# EC544.net
KiCad netlist of a schematic drawn in EAGLE
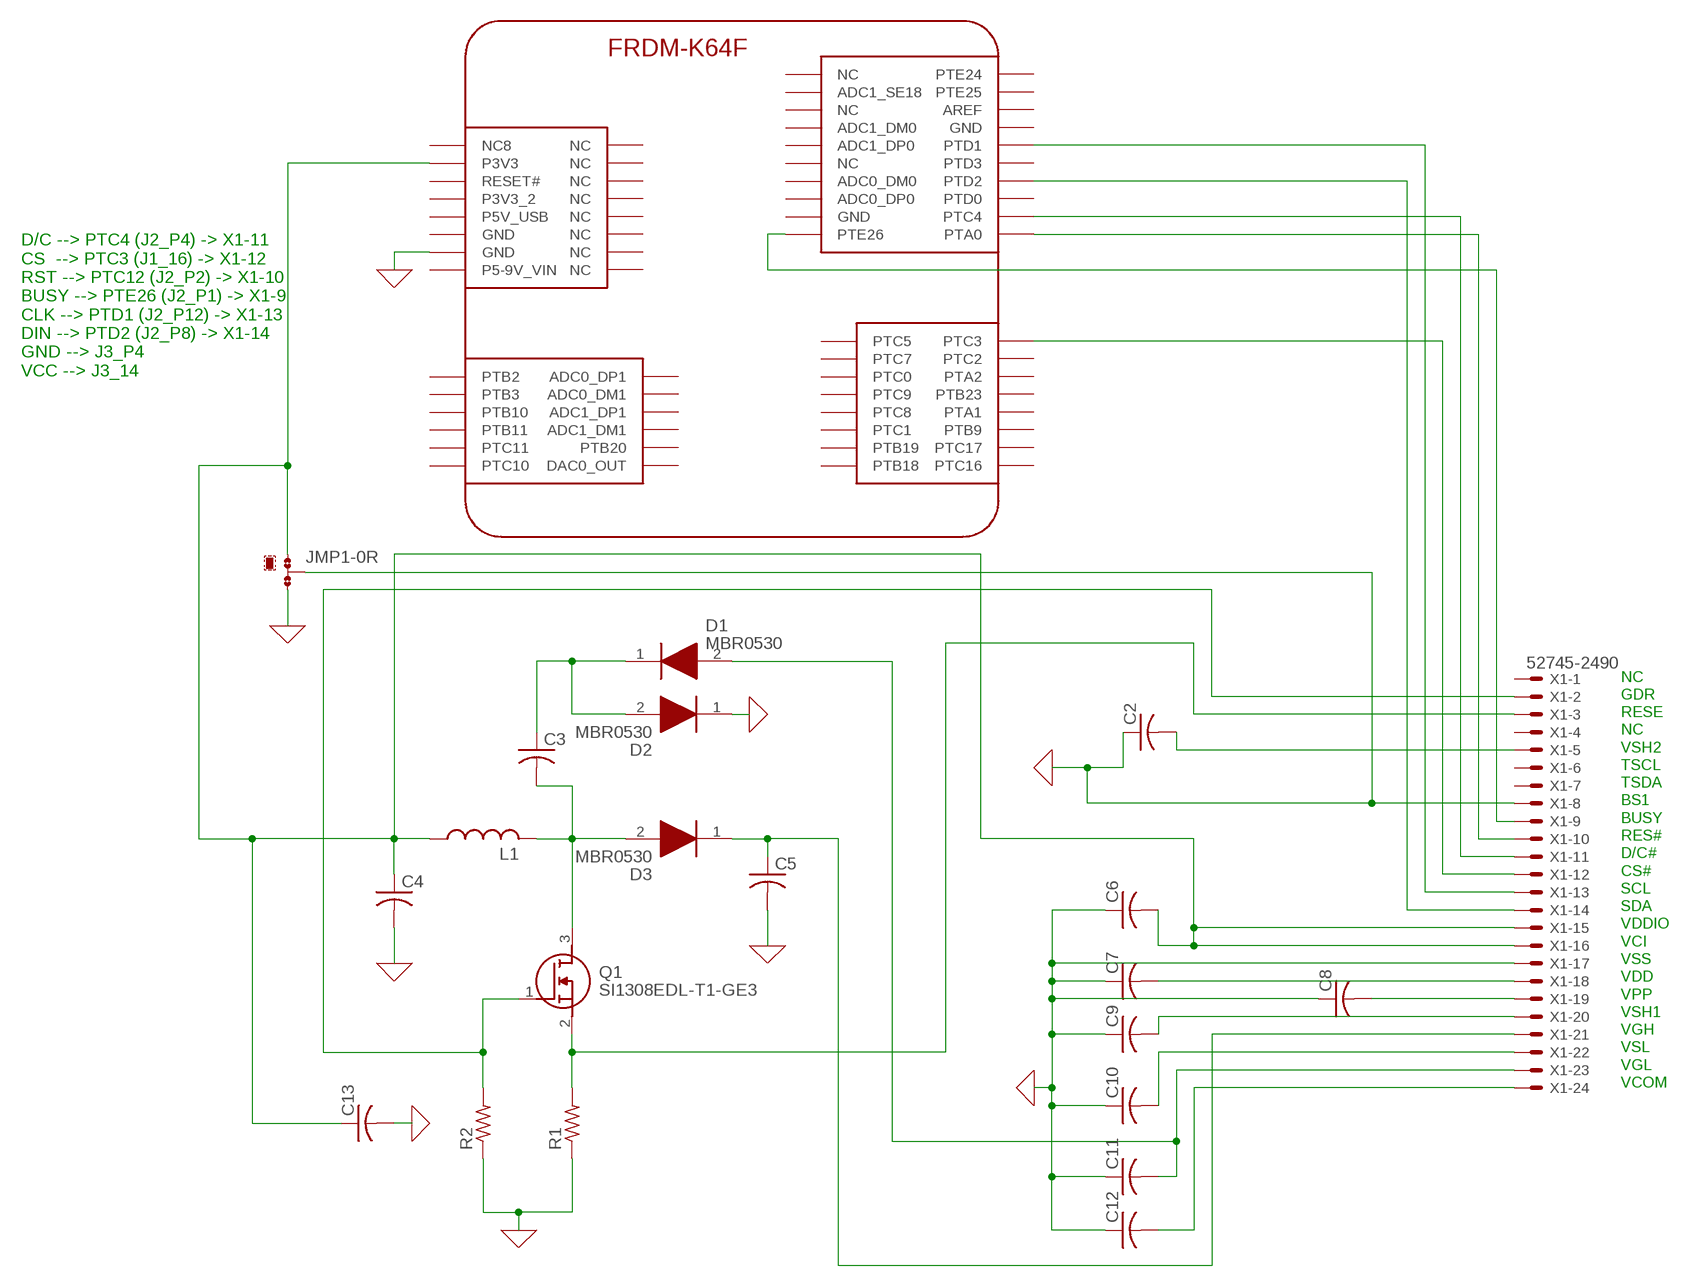
[diagram p0: schematic, sheet 1]

(export (version "E")
  (design (tool "Eeschema 10.0.6"))
  (components
    (comp (ref "C2")
      (value "C-US025-024X044")
      (footprint "eagle-import:C025-024X044")
      (libsource (lib "eagle-import") (part "C-US025-024X044"))
    )
    (comp (ref "C3")
      (value "C-US025-024X044")
      (footprint "eagle-import:C025-024X044")
      (libsource (lib "eagle-import") (part "C-US025-024X044"))
    )
    (comp (ref "C4")
      (value "C-US025-024X044")
      (footprint "eagle-import:C025-024X044")
      (libsource (lib "eagle-import") (part "C-US025-024X044"))
    )
    (comp (ref "C5")
      (value "C-US025-024X044")
      (footprint "eagle-import:C025-024X044")
      (libsource (lib "eagle-import") (part "C-US025-024X044"))
    )
    (comp (ref "C6")
      (value "C-US025-024X044")
      (footprint "eagle-import:C025-024X044")
      (libsource (lib "eagle-import") (part "C-US025-024X044"))
    )
    (comp (ref "C7")
      (value "C-US025-024X044")
      (footprint "eagle-import:C025-024X044")
      (libsource (lib "eagle-import") (part "C-US025-024X044"))
    )
    (comp (ref "C8")
      (value "C-US025-024X044")
      (footprint "eagle-import:C025-024X044")
      (libsource (lib "eagle-import") (part "C-US025-024X044"))
    )
    (comp (ref "C9")
      (value "C-US025-024X044")
      (footprint "eagle-import:C025-024X044")
      (libsource (lib "eagle-import") (part "C-US025-024X044"))
    )
    (comp (ref "C10")
      (value "C-US025-024X044")
      (footprint "eagle-import:C025-024X044")
      (libsource (lib "eagle-import") (part "C-US025-024X044"))
    )
    (comp (ref "C11")
      (value "C-US025-024X044")
      (footprint "eagle-import:C025-024X044")
      (libsource (lib "eagle-import") (part "C-US025-024X044"))
    )
    (comp (ref "C12")
      (value "C-US025-024X044")
      (footprint "eagle-import:C025-024X044")
      (libsource (lib "eagle-import") (part "C-US025-024X044"))
    )
    (comp (ref "C13")
      (value "C-US025-024X044")
      (footprint "eagle-import:C025-024X044")
      (libsource (lib "eagle-import") (part "C-US025-024X044"))
    )
    (comp (ref "D1")
      (value "MBR0530")
      (footprint "eagle-import:SOD3716X135N")
      (fields (field (name "MOUSER_PART_NUMBER") "512-MBR0530"))
      (libsource (lib "eagle-import") (part "MBR0530"))
    )
    (comp (ref "D2")
      (value "MBR0530")
      (footprint "eagle-import:SOD3716X135N")
      (fields (field (name "MOUSER_PART_NUMBER") "512-MBR0530"))
      (libsource (lib "eagle-import") (part "MBR0530"))
    )
    (comp (ref "D3")
      (value "MBR0530")
      (footprint "eagle-import:SOD3716X135N")
      (fields (field (name "MOUSER_PART_NUMBER") "512-MBR0530"))
      (libsource (lib "eagle-import") (part "MBR0530"))
    )
    (comp (ref "FRDM1")
      (value "FRDM-K64FNORMAL")
      (footprint "eagle-import:FRDM_K64F")
      (libsource (lib "eagle-import") (part "FRDM-K64FNORMAL"))
    )
    (comp (ref "JMP1")
      (value "0R-JUMPA")
      (footprint "eagle-import:A0R-JMP")
      (libsource (lib "eagle-import") (part "0R-JUMPA"))
    )
    (comp (ref "L1")
      (value "L-USPIS2816")
      (footprint "eagle-import:PIS2816")
      (libsource (lib "eagle-import") (part "L-USPIS2816"))
    )
    (comp (ref "Q1")
      (value "SI1308EDL-T1-GE3")
      (footprint "eagle-import:SOT65P210X110-3N")
      (fields
        (field (name "MANUFACTURER_PART_NUMBER") "Si1308EDL-T1-GE3")
        (field (name "MOUSER_PART_NUMBER") "78-SI1308EDL-T1-GE3")
      )
      (libsource (lib "eagle-import") (part "SI1308EDL-T1-GE3"))
    )
    (comp (ref "R1")
      (value "R-US_0204/5")
      (footprint "eagle-import:0204_5")
      (libsource (lib "eagle-import") (part "R-US_0204/5"))
    )
    (comp (ref "R2")
      (value "R-US_0204/5")
      (footprint "eagle-import:0204_5")
      (libsource (lib "eagle-import") (part "R-US_0204/5"))
    )
    (comp (ref "X1")
      (value "52745-2490")
      (footprint "eagle-import:52745-2490")
      (fields (field (name "MF") "MOLEX"))
      (libsource (lib "eagle-import") (part "52745-2490"))
    )
  )
  (nets
    (net (code "1") (name "GND") (class "Default")
      (node (ref "C10") (pin "1") (pinfunction "1_1") (pintype "passive"))
      (node (ref "C11") (pin "1") (pinfunction "1_1") (pintype "passive"))
      (node (ref "C12") (pin "1") (pinfunction "1_1") (pintype "passive"))
      (node (ref "C13") (pin "2") (pinfunction "2_2") (pintype "passive"))
      (node (ref "C2") (pin "1") (pinfunction "1_1") (pintype "passive"))
      (node (ref "C4") (pin "2") (pinfunction "2_2") (pintype "passive"))
      (node (ref "C5") (pin "2") (pinfunction "2_2") (pintype "passive"))
      (node (ref "C6") (pin "1") (pinfunction "1_1") (pintype "passive"))
      (node (ref "C7") (pin "1") (pinfunction "1_1") (pintype "passive"))
      (node (ref "C8") (pin "1") (pinfunction "1_1") (pintype "passive"))
      (node (ref "C9") (pin "1") (pinfunction "1_1") (pintype "passive"))
      (node (ref "D2") (pin "1") (pinfunction "K_1") (pintype "bidirectional"))
      (node (ref "FRDM1") (pin "J3.14") (pinfunction "GND_J3.14") (pintype "bidirectional"))
      (node (ref "JMP1") (pin "2") (pinfunction "2_2") (pintype "passive"))
      (node (ref "JMP1") (pin "3") (pinfunction "3_3") (pintype "passive"))
      (node (ref "R1") (pin "1") (pinfunction "1_1") (pintype "passive"))
      (node (ref "R2") (pin "1") (pinfunction "1_1") (pintype "passive"))
      (node (ref "X1") (pin "17") (pinfunction "S_17") (pintype "passive"))
      (node (ref "X1") (pin "8") (pinfunction "S_8") (pintype "passive"))
    )
    (net (code "2") (name "Net-(D1-A)") (class "Default")
      (node (ref "C11") (pin "2") (pinfunction "2_2") (pintype "passive"))
      (node (ref "D1") (pin "2") (pinfunction "A_2") (pintype "bidirectional"))
      (node (ref "X1") (pin "23") (pinfunction "S_23") (pintype "passive"))
    )
    (net (code "3") (name "Net-(D1-K)") (class "Default")
      (node (ref "C3") (pin "1") (pinfunction "1_1") (pintype "passive"))
      (node (ref "D1") (pin "1") (pinfunction "K_1") (pintype "bidirectional"))
      (node (ref "D2") (pin "2") (pinfunction "A_2") (pintype "bidirectional"))
    )
    (net (code "4") (name "Net-(D3-A)") (class "Default")
      (node (ref "C3") (pin "2") (pinfunction "2_2") (pintype "passive"))
      (node (ref "D3") (pin "2") (pinfunction "A_2") (pintype "bidirectional"))
      (node (ref "L1") (pin "2") (pinfunction "2_2") (pintype "passive"))
      (node (ref "Q1") (pin "3") (pinfunction "D_3") (pintype "bidirectional"))
    )
    (net (code "5") (name "Net-(D3-K)") (class "Default")
      (node (ref "C5") (pin "1") (pinfunction "1_1") (pintype "passive"))
      (node (ref "D3") (pin "1") (pinfunction "K_1") (pintype "bidirectional"))
      (node (ref "X1") (pin "21") (pinfunction "S_21") (pintype "passive"))
    )
    (net (code "6") (name "Net-(FRDM1-P3V3)") (class "Default")
      (node (ref "C13") (pin "1") (pinfunction "1_1") (pintype "passive"))
      (node (ref "C4") (pin "1") (pinfunction "1_1") (pintype "passive"))
      (node (ref "C6") (pin "2") (pinfunction "2_2") (pintype "passive"))
      (node (ref "FRDM1") (pin "J3.4") (pinfunction "P3V3_J3.4") (pintype "bidirectional"))
      (node (ref "JMP1") (pin "1") (pinfunction "1_1") (pintype "passive"))
      (node (ref "L1") (pin "1") (pinfunction "1_1") (pintype "passive"))
      (node (ref "X1") (pin "15") (pinfunction "S_15") (pintype "passive"))
      (node (ref "X1") (pin "16") (pinfunction "S_16") (pintype "passive"))
    )
    (net (code "7") (name "Net-(FRDM1-PTA0)") (class "Default")
      (node (ref "FRDM1") (pin "J2.2") (pinfunction "PTA0_J2.2") (pintype "bidirectional"))
      (node (ref "X1") (pin "10") (pinfunction "S_10") (pintype "passive"))
    )
    (net (code "8") (name "Net-(FRDM1-PTC3)") (class "Default")
      (node (ref "FRDM1") (pin "J1.16") (pinfunction "PTC3_J1.16") (pintype "bidirectional"))
      (node (ref "X1") (pin "12") (pinfunction "S_12") (pintype "passive"))
    )
    (net (code "9") (name "Net-(FRDM1-PTC4)") (class "Default")
      (node (ref "FRDM1") (pin "J2.4") (pinfunction "PTC4_J2.4") (pintype "bidirectional"))
      (node (ref "X1") (pin "11") (pinfunction "S_11") (pintype "passive"))
    )
    (net (code "10") (name "Net-(FRDM1-PTD1)") (class "Default")
      (node (ref "FRDM1") (pin "J2.12") (pinfunction "PTD1_J2.12") (pintype "bidirectional"))
      (node (ref "X1") (pin "13") (pinfunction "S_13") (pintype "passive"))
    )
    (net (code "11") (name "Net-(FRDM1-PTD2)") (class "Default")
      (node (ref "FRDM1") (pin "J2.8") (pinfunction "PTD2_J2.8") (pintype "bidirectional"))
      (node (ref "X1") (pin "14") (pinfunction "S_14") (pintype "passive"))
    )
    (net (code "12") (name "Net-(FRDM1-PTE26)") (class "Default")
      (node (ref "FRDM1") (pin "J2.1") (pinfunction "PTE26_J2.1") (pintype "bidirectional"))
      (node (ref "X1") (pin "9") (pinfunction "S_9") (pintype "passive"))
    )
    (net (code "13") (name "Net-(Q1-G)") (class "Default")
      (node (ref "Q1") (pin "1") (pinfunction "G_1") (pintype "bidirectional"))
      (node (ref "R2") (pin "2") (pinfunction "2_2") (pintype "passive"))
      (node (ref "X1") (pin "2") (pinfunction "S_2") (pintype "passive"))
    )
    (net (code "14") (name "Net-(Q1-S)") (class "Default")
      (node (ref "Q1") (pin "2") (pinfunction "S_2") (pintype "bidirectional"))
      (node (ref "R1") (pin "2") (pinfunction "2_2") (pintype "passive"))
      (node (ref "X1") (pin "3") (pinfunction "S_3") (pintype "passive"))
    )
    (net (code "15") (name "Net-(X1J-S)") (class "Default")
      (node (ref "C7") (pin "2") (pinfunction "2_2") (pintype "passive"))
      (node (ref "X1") (pin "18") (pinfunction "S_18") (pintype "passive"))
    )
    (net (code "16") (name "Net-(X1K-S)") (class "Default")
      (node (ref "C8") (pin "2") (pinfunction "2_2") (pintype "passive"))
      (node (ref "X1") (pin "19") (pinfunction "S_19") (pintype "passive"))
    )
    (net (code "17") (name "Net-(X1M-S)") (class "Default")
      (node (ref "C9") (pin "2") (pinfunction "2_2") (pintype "passive"))
      (node (ref "X1") (pin "20") (pinfunction "S_20") (pintype "passive"))
    )
    (net (code "18") (name "Net-(X1O-S)") (class "Default")
      (node (ref "C10") (pin "2") (pinfunction "2_2") (pintype "passive"))
      (node (ref "X1") (pin "22") (pinfunction "S_22") (pintype "passive"))
    )
    (net (code "19") (name "Net-(X1Q-S)") (class "Default")
      (node (ref "C12") (pin "2") (pinfunction "2_2") (pintype "passive"))
      (node (ref "X1") (pin "24") (pinfunction "S_24") (pintype "passive"))
    )
    (net (code "20") (name "Net-(X1T-S)") (class "Default")
      (node (ref "C2") (pin "2") (pinfunction "2_2") (pintype "passive"))
      (node (ref "X1") (pin "5") (pinfunction "S_5") (pintype "passive"))
    )
    (net (code "21") (name "unconnected-(FRDM1-ADC0_DM0-PadJ2.7)") (class "Default")
      (node (ref "FRDM1") (pin "J2.7") (pinfunction "ADC0_DM0_J2.7") (pintype "bidirectional"))
    )
    (net (code "22") (name "unconnected-(FRDM1-ADC0_DM1-PadJ4.3)") (class "Default")
      (node (ref "FRDM1") (pin "J4.3") (pinfunction "ADC0_DM1_J4.3") (pintype "bidirectional"))
    )
    (net (code "23") (name "unconnected-(FRDM1-ADC0_DP0-PadJ2.5)") (class "Default")
      (node (ref "FRDM1") (pin "J2.5") (pinfunction "ADC0_DP0_J2.5") (pintype "bidirectional"))
    )
    (net (code "24") (name "unconnected-(FRDM1-ADC0_DP1-PadJ4.1)") (class "Default")
      (node (ref "FRDM1") (pin "J4.1") (pinfunction "ADC0_DP1_J4.1") (pintype "bidirectional"))
    )
    (net (code "25") (name "unconnected-(FRDM1-ADC1_DM0-PadJ2.13)") (class "Default")
      (node (ref "FRDM1") (pin "J2.13") (pinfunction "ADC1_DM0_J2.13") (pintype "bidirectional"))
    )
    (net (code "26") (name "unconnected-(FRDM1-ADC1_DM1-PadJ4.7)") (class "Default")
      (node (ref "FRDM1") (pin "J4.7") (pinfunction "ADC1_DM1_J4.7") (pintype "bidirectional"))
    )
    (net (code "27") (name "unconnected-(FRDM1-ADC1_DP0-PadJ2.11)") (class "Default")
      (node (ref "FRDM1") (pin "J2.11") (pinfunction "ADC1_DP0_J2.11") (pintype "bidirectional"))
    )
    (net (code "28") (name "unconnected-(FRDM1-ADC1_DP1-PadJ4.5)") (class "Default")
      (node (ref "FRDM1") (pin "J4.5") (pinfunction "ADC1_DP1_J4.5") (pintype "bidirectional"))
    )
    (net (code "29") (name "unconnected-(FRDM1-ADC1_SE18-PadJ2.17)") (class "Default")
      (node (ref "FRDM1") (pin "J2.17") (pinfunction "ADC1_SE18_J2.17") (pintype "bidirectional"))
    )
    (net (code "30") (name "unconnected-(FRDM1-AREF-PadJ2.16)") (class "Default")
      (node (ref "FRDM1") (pin "J2.16") (pinfunction "AREF_J2.16") (pintype "bidirectional"))
    )
    (net (code "31") (name "unconnected-(FRDM1-DAC0_OUT-PadJ4.11)") (class "Default")
      (node (ref "FRDM1") (pin "J4.11") (pinfunction "DAC0_OUT_J4.11") (pintype "bidirectional"))
    )
    (net (code "32") (name "unconnected-(FRDM1-GND-PadJ2.3)") (class "Default")
      (node (ref "FRDM1") (pin "J2.3") (pinfunction "GND_J2.3") (pintype "bidirectional"))
    )
    (net (code "33") (name "unconnected-(FRDM1-GND-PadJ2.14)") (class "Default")
      (node (ref "FRDM1") (pin "J2.14") (pinfunction "GND_J2.14") (pintype "bidirectional"))
    )
    (net (code "34") (name "unconnected-(FRDM1-GND-PadJ3.12)") (class "Default")
      (node (ref "FRDM1") (pin "J3.12") (pinfunction "GND_J3.12") (pintype "bidirectional"))
    )
    (net (code "35") (name "unconnected-(FRDM1-NC-PadJ2.9)") (class "Default")
      (node (ref "FRDM1") (pin "J2.9") (pinfunction "NC_J2.9") (pintype "bidirectional"))
    )
    (net (code "36") (name "unconnected-(FRDM1-NC-PadJ2.15)") (class "Default")
      (node (ref "FRDM1") (pin "J2.15") (pinfunction "NC_J2.15") (pintype "bidirectional"))
    )
    (net (code "37") (name "unconnected-(FRDM1-NC-PadJ2.19)") (class "Default")
      (node (ref "FRDM1") (pin "J2.19") (pinfunction "NC_J2.19") (pintype "bidirectional"))
    )
    (net (code "38") (name "unconnected-(FRDM1-NC-PadJ3.1)") (class "Default")
      (node (ref "FRDM1") (pin "J3.1") (pinfunction "NC_J3.1") (pintype "bidirectional"))
    )
    (net (code "39") (name "unconnected-(FRDM1-NC-PadJ3.2)") (class "Default")
      (node (ref "FRDM1") (pin "J3.2") (pinfunction "NC_J3.2") (pintype "bidirectional"))
    )
    (net (code "40") (name "unconnected-(FRDM1-NC-PadJ3.3)") (class "Default")
      (node (ref "FRDM1") (pin "J3.3") (pinfunction "NC_J3.3") (pintype "bidirectional"))
    )
    (net (code "41") (name "unconnected-(FRDM1-NC-PadJ3.5)") (class "Default")
      (node (ref "FRDM1") (pin "J3.5") (pinfunction "NC_J3.5") (pintype "bidirectional"))
    )
    (net (code "42") (name "unconnected-(FRDM1-NC-PadJ3.7)") (class "Default")
      (node (ref "FRDM1") (pin "J3.7") (pinfunction "NC_J3.7") (pintype "bidirectional"))
    )
    (net (code "43") (name "unconnected-(FRDM1-NC-PadJ3.9)") (class "Default")
      (node (ref "FRDM1") (pin "J3.9") (pinfunction "NC_J3.9") (pintype "bidirectional"))
    )
    (net (code "44") (name "unconnected-(FRDM1-NC-PadJ3.11)") (class "Default")
      (node (ref "FRDM1") (pin "J3.11") (pinfunction "NC_J3.11") (pintype "bidirectional"))
    )
    (net (code "45") (name "unconnected-(FRDM1-NC-PadJ3.13)") (class "Default")
      (node (ref "FRDM1") (pin "J3.13") (pinfunction "NC_J3.13") (pintype "bidirectional"))
    )
    (net (code "46") (name "unconnected-(FRDM1-NC8-PadJ3.15)") (class "Default")
      (node (ref "FRDM1") (pin "J3.15") (pinfunction "NC8_J3.15") (pintype "bidirectional"))
    )
    (net (code "47") (name "unconnected-(FRDM1-P3V3_2-PadJ3.8)") (class "Default")
      (node (ref "FRDM1") (pin "J3.8") (pinfunction "P3V3_2_J3.8") (pintype "bidirectional"))
    )
    (net (code "48") (name "unconnected-(FRDM1-P5-9V_VIN-PadJ3.16)") (class "Default")
      (node (ref "FRDM1") (pin "J3.16") (pinfunction "P5-9V_VIN_J3.16") (pintype "bidirectional"))
    )
    (net (code "49") (name "unconnected-(FRDM1-P5V_USB-PadJ3.10)") (class "Default")
      (node (ref "FRDM1") (pin "J3.10") (pinfunction "P5V_USB_J3.10") (pintype "bidirectional"))
    )
    (net (code "50") (name "unconnected-(FRDM1-PTA1-PadJ1.8)") (class "Default")
      (node (ref "FRDM1") (pin "J1.8") (pinfunction "PTA1_J1.8") (pintype "bidirectional"))
    )
    (net (code "51") (name "unconnected-(FRDM1-PTA2-PadJ1.12)") (class "Default")
      (node (ref "FRDM1") (pin "J1.12") (pinfunction "PTA2_J1.12") (pintype "bidirectional"))
    )
    (net (code "52") (name "unconnected-(FRDM1-PTB2-PadJ4.2)") (class "Default")
      (node (ref "FRDM1") (pin "J4.2") (pinfunction "PTB2_J4.2") (pintype "bidirectional"))
    )
    (net (code "53") (name "unconnected-(FRDM1-PTB3-PadJ4.4)") (class "Default")
      (node (ref "FRDM1") (pin "J4.4") (pinfunction "PTB3_J4.4") (pintype "bidirectional"))
    )
    (net (code "54") (name "unconnected-(FRDM1-PTB9-PadJ1.6)") (class "Default")
      (node (ref "FRDM1") (pin "J1.6") (pinfunction "PTB9_J1.6") (pintype "bidirectional"))
    )
    (net (code "55") (name "unconnected-(FRDM1-PTB10-PadJ4.6)") (class "Default")
      (node (ref "FRDM1") (pin "J4.6") (pinfunction "PTB10_J4.6") (pintype "bidirectional"))
    )
    (net (code "56") (name "unconnected-(FRDM1-PTB11-PadJ4.8)") (class "Default")
      (node (ref "FRDM1") (pin "J4.8") (pinfunction "PTB11_J4.8") (pintype "bidirectional"))
    )
    (net (code "57") (name "unconnected-(FRDM1-PTB18-PadJ1.1)") (class "Default")
      (node (ref "FRDM1") (pin "J1.1") (pinfunction "PTB18_J1.1") (pintype "bidirectional"))
    )
    (net (code "58") (name "unconnected-(FRDM1-PTB19-PadJ1.3)") (class "Default")
      (node (ref "FRDM1") (pin "J1.3") (pinfunction "PTB19_J1.3") (pintype "bidirectional"))
    )
    (net (code "59") (name "unconnected-(FRDM1-PTB20-PadJ4.9)") (class "Default")
      (node (ref "FRDM1") (pin "J4.9") (pinfunction "PTB20_J4.9") (pintype "bidirectional"))
    )
    (net (code "60") (name "unconnected-(FRDM1-PTB23-PadJ1.10)") (class "Default")
      (node (ref "FRDM1") (pin "J1.10") (pinfunction "PTB23_J1.10") (pintype "bidirectional"))
    )
    (net (code "61") (name "unconnected-(FRDM1-PTC0-PadJ1.11)") (class "Default")
      (node (ref "FRDM1") (pin "J1.11") (pinfunction "PTC0_J1.11") (pintype "bidirectional"))
    )
    (net (code "62") (name "unconnected-(FRDM1-PTC1-PadJ1.5)") (class "Default")
      (node (ref "FRDM1") (pin "J1.5") (pinfunction "PTC1_J1.5") (pintype "bidirectional"))
    )
    (net (code "63") (name "unconnected-(FRDM1-PTC2-PadJ1.14)") (class "Default")
      (node (ref "FRDM1") (pin "J1.14") (pinfunction "PTC2_J1.14") (pintype "bidirectional"))
    )
    (net (code "64") (name "unconnected-(FRDM1-PTC5-PadJ1.15)") (class "Default")
      (node (ref "FRDM1") (pin "J1.15") (pinfunction "PTC5_J1.15") (pintype "bidirectional"))
    )
    (net (code "65") (name "unconnected-(FRDM1-PTC7-PadJ1.13)") (class "Default")
      (node (ref "FRDM1") (pin "J1.13") (pinfunction "PTC7_J1.13") (pintype "bidirectional"))
    )
    (net (code "66") (name "unconnected-(FRDM1-PTC8-PadJ1.7)") (class "Default")
      (node (ref "FRDM1") (pin "J1.7") (pinfunction "PTC8_J1.7") (pintype "bidirectional"))
    )
    (net (code "67") (name "unconnected-(FRDM1-PTC9-PadJ1.9)") (class "Default")
      (node (ref "FRDM1") (pin "J1.9") (pinfunction "PTC9_J1.9") (pintype "bidirectional"))
    )
    (net (code "68") (name "unconnected-(FRDM1-PTC10-PadJ4.12)") (class "Default")
      (node (ref "FRDM1") (pin "J4.12") (pinfunction "PTC10_J4.12") (pintype "bidirectional"))
    )
    (net (code "69") (name "unconnected-(FRDM1-PTC11-PadJ4.10)") (class "Default")
      (node (ref "FRDM1") (pin "J4.10") (pinfunction "PTC11_J4.10") (pintype "bidirectional"))
    )
    (net (code "70") (name "unconnected-(FRDM1-PTC16-PadJ1.2)") (class "Default")
      (node (ref "FRDM1") (pin "J1.2") (pinfunction "PTC16_J1.2") (pintype "bidirectional"))
    )
    (net (code "71") (name "unconnected-(FRDM1-PTC17-PadJ1.4)") (class "Default")
      (node (ref "FRDM1") (pin "J1.4") (pinfunction "PTC17_J1.4") (pintype "bidirectional"))
    )
    (net (code "72") (name "unconnected-(FRDM1-PTD0-PadJ2.6)") (class "Default")
      (node (ref "FRDM1") (pin "J2.6") (pinfunction "PTD0_J2.6") (pintype "bidirectional"))
    )
    (net (code "73") (name "unconnected-(FRDM1-PTD3-PadJ2.10)") (class "Default")
      (node (ref "FRDM1") (pin "J2.10") (pinfunction "PTD3_J2.10") (pintype "bidirectional"))
    )
    (net (code "74") (name "unconnected-(FRDM1-PTE24-PadJ2.20)") (class "Default")
      (node (ref "FRDM1") (pin "J2.20") (pinfunction "PTE24_J2.20") (pintype "bidirectional"))
    )
    (net (code "75") (name "unconnected-(FRDM1-PTE25-PadJ2.18)") (class "Default")
      (node (ref "FRDM1") (pin "J2.18") (pinfunction "PTE25_J2.18") (pintype "bidirectional"))
    )
    (net (code "76") (name "unconnected-(FRDM1-RESET#-PadJ3.6)") (class "Default")
      (node (ref "FRDM1") (pin "J3.6") (pinfunction "RESET#_J3.6") (pintype "bidirectional"))
    )
    (net (code "77") (name "unconnected-(X1A-S-Pad1)") (class "Default")
      (node (ref "X1") (pin "1") (pinfunction "S_1") (pintype "passive"))
    )
    (net (code "78") (name "unconnected-(X1S-S-Pad4)") (class "Default")
      (node (ref "X1") (pin "4") (pinfunction "S_4") (pintype "passive"))
    )
    (net (code "79") (name "unconnected-(X1U-S-Pad6)") (class "Default")
      (node (ref "X1") (pin "6") (pinfunction "S_6") (pintype "passive"))
    )
    (net (code "80") (name "unconnected-(X1V-S-Pad7)") (class "Default")
      (node (ref "X1") (pin "7") (pinfunction "S_7") (pintype "passive"))
    )
  )
)
